# BT_ADOL_R4.net
KiCad netlist of a schematic drawn in EAGLE
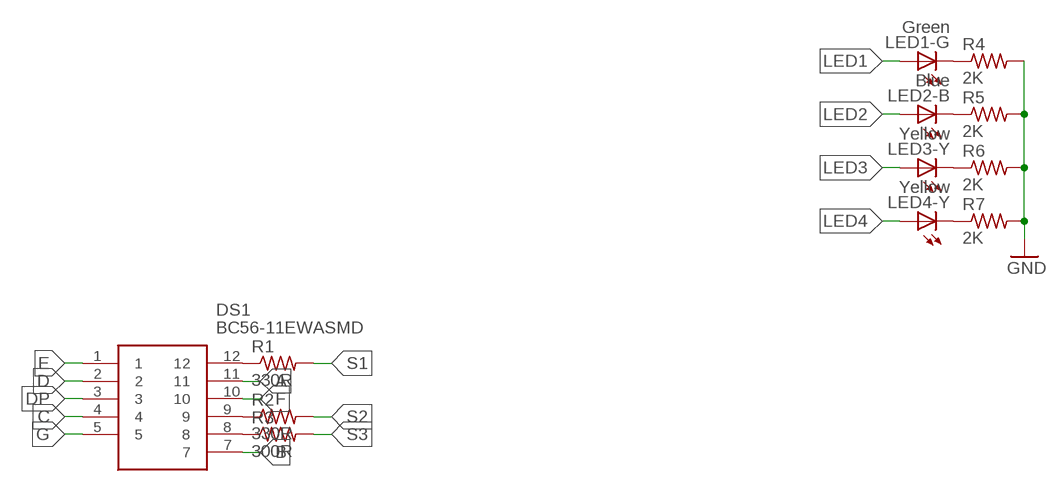
[diagram p0: schematic, sheet 1, part 1 of 2]
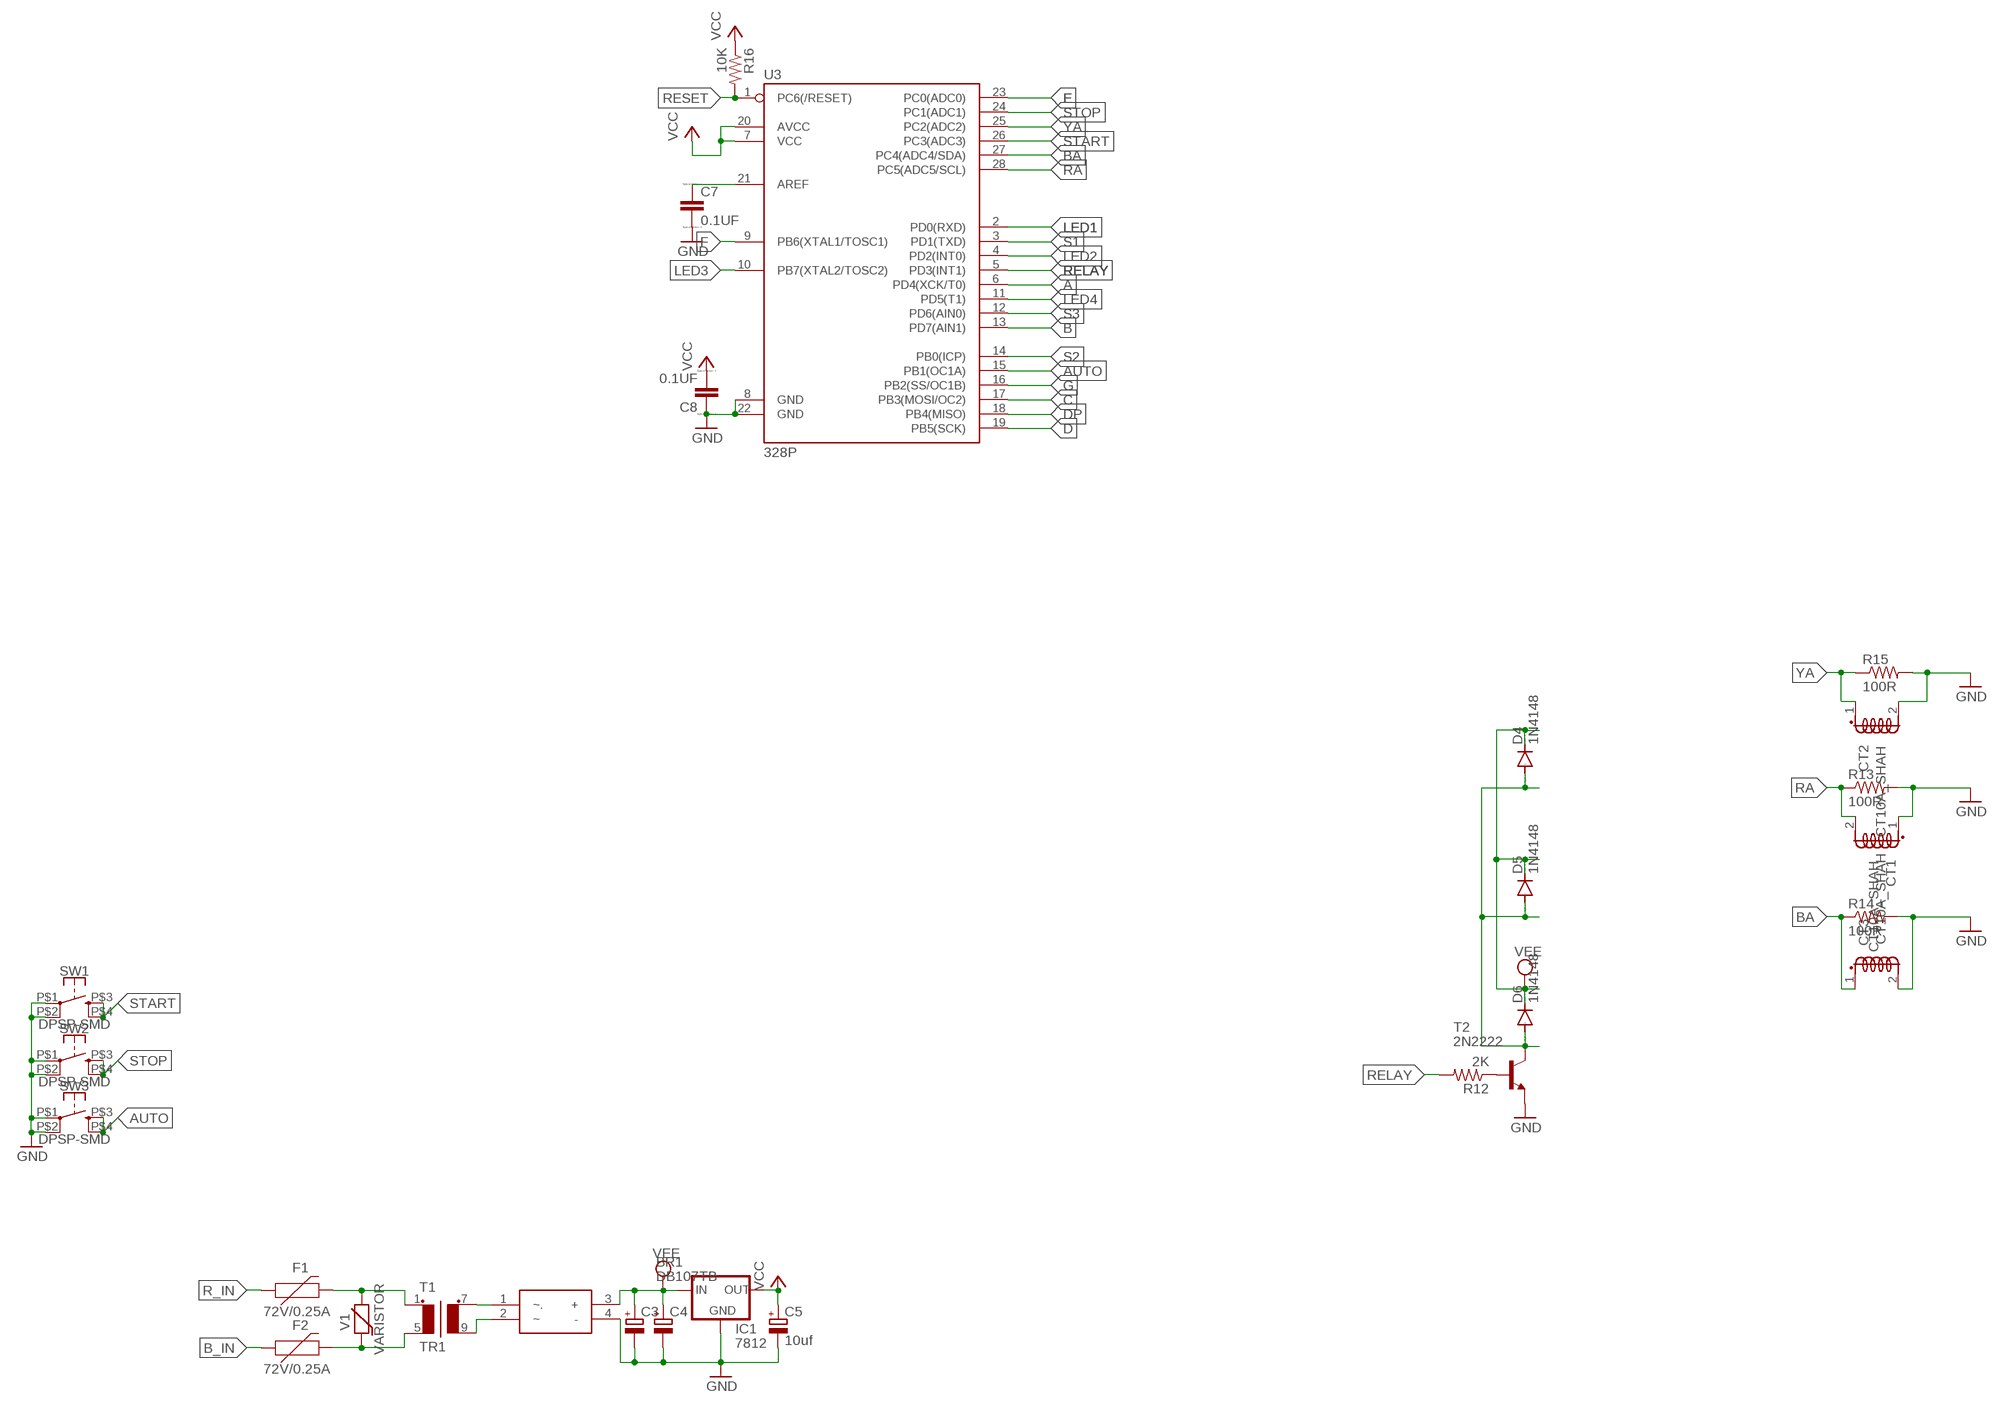
[diagram p1: schematic, sheet 1, part 2 of 2]

(export (version "E")
  (design (tool "Eeschema 10.0.6"))
  (components
    (comp (ref "BR1")
      (value "DB107TB")
      (footprint "eagle-import:DIP845W60P510L815H400Q4N")
      (libsource (lib "eagle-import") (part "DB107TB"))
    )
    (comp (ref "C3")
      (value "CPOL-EUE3.5-10")
      (footprint "eagle-import:E3,5-10")
      (libsource (lib "eagle-import") (part "resistor_348_CPOL-EUE3.5-10"))
    )
    (comp (ref "C4")
      (value "CPOL-EUE3.5-10")
      (footprint "eagle-import:E3,5-10")
      (libsource (lib "eagle-import") (part "resistor_348_CPOL-EUE3.5-10"))
    )
    (comp (ref "C5")
      (value "10uf")
      (footprint "eagle-import:E2-4")
      (libsource (lib "eagle-import") (part "CPOL-EUE2-4"))
    )
    (comp (ref "C7")
      (value "0.1UF")
      (footprint "eagle-import:C1206")
      (libsource (lib "eagle-import") (part "CC1206"))
    )
    (comp (ref "C8")
      (value "0.1UF")
      (footprint "eagle-import:C1206")
      (libsource (lib "eagle-import") (part "CC1206"))
    )
    (comp (ref "CT1")
      (value "CT10A_SHAH")
      (footprint "eagle-import:10A_SHAH")
      (libsource (lib "eagle-import") (part "CT10A_SHAH"))
    )
    (comp (ref "CT2")
      (value "CT10A_SHAH")
      (footprint "eagle-import:10A_SHAH")
      (libsource (lib "eagle-import") (part "CT10A_SHAH"))
    )
    (comp (ref "CT3")
      (value "CT10A_SHAH")
      (footprint "eagle-import:10A_SHAH")
      (libsource (lib "eagle-import") (part "CT10A_SHAH"))
    )
    (comp (ref "D4")
      (value "1N4148")
      (footprint "eagle-import:MINIMELF")
      (libsource (lib "eagle-import") (part "DIODE-MINIMELF"))
    )
    (comp (ref "D5")
      (value "1N4148")
      (footprint "eagle-import:MINIMELF")
      (libsource (lib "eagle-import") (part "DIODE-MINIMELF"))
    )
    (comp (ref "D6")
      (value "1N4148")
      (footprint "eagle-import:MINIMELF")
      (libsource (lib "eagle-import") (part "DIODE-MINIMELF"))
    )
    (comp (ref "DS1")
      (value "BC56-11EWASMD")
      (footprint "eagle-import:7SEGMENT-SMD")
      (libsource (lib "eagle-import") (part "BC56-11EWASMD"))
    )
    (comp (ref "F1")
      (value "72V/0.25A")
      (footprint "eagle-import:PTH")
      (libsource (lib "eagle-import") (part "PPTC_PTH"))
    )
    (comp (ref "F2")
      (value "72V/0.25A")
      (footprint "eagle-import:PTH")
      (libsource (lib "eagle-import") (part "PPTC_PTH"))
    )
    (comp (ref "IC1")
      (value "7812")
      (footprint "eagle-import:78XXS")
      (libsource (lib "eagle-import") (part "78XXS"))
    )
    (comp (ref "LED1-G")
      (value "Green")
      (footprint "eagle-import:LED3MM")
      (libsource (lib "eagle-import") (part "LED3MM"))
    )
    (comp (ref "LED2-B")
      (value "Blue")
      (footprint "eagle-import:LED3MM")
      (libsource (lib "eagle-import") (part "LED3MM"))
    )
    (comp (ref "LED3-Y")
      (value "Yellow")
      (footprint "eagle-import:LED3MM")
      (libsource (lib "eagle-import") (part "LED3MM"))
    )
    (comp (ref "LED4-Y")
      (value "Yellow")
      (footprint "eagle-import:LED3MM")
      (libsource (lib "eagle-import") (part "LED3MM"))
    )
    (comp (ref "R1")
      (value "330R")
      (footprint "eagle-import:R1206")
      (libsource (lib "eagle-import") (part "rcl_334_R-US_R1206"))
    )
    (comp (ref "R2")
      (value "330R")
      (footprint "eagle-import:R1206")
      (libsource (lib "eagle-import") (part "rcl_334_R-US_R1206"))
    )
    (comp (ref "R3")
      (value "300R")
      (footprint "eagle-import:R1206")
      (libsource (lib "eagle-import") (part "rcl_334_R-US_R1206"))
    )
    (comp (ref "R4")
      (value "2K")
      (footprint "eagle-import:R1206")
      (libsource (lib "eagle-import") (part "rcl_334_R-US_R1206"))
    )
    (comp (ref "R5")
      (value "2K")
      (footprint "eagle-import:R1206")
      (libsource (lib "eagle-import") (part "rcl_334_R-US_R1206"))
    )
    (comp (ref "R6")
      (value "2K")
      (footprint "eagle-import:R1206")
      (libsource (lib "eagle-import") (part "rcl_334_R-US_R1206"))
    )
    (comp (ref "R7")
      (value "2K")
      (footprint "eagle-import:R1206")
      (libsource (lib "eagle-import") (part "rcl_334_R-US_R1206"))
    )
    (comp (ref "R12")
      (value "2K")
      (footprint "eagle-import:M1206")
      (libsource (lib "eagle-import") (part "R-US_M1206"))
    )
    (comp (ref "R13")
      (value "100R")
      (footprint "eagle-import:M1206")
      (libsource (lib "eagle-import") (part "R-US_M1206"))
    )
    (comp (ref "R14")
      (value "100R")
      (footprint "eagle-import:M1206")
      (libsource (lib "eagle-import") (part "R-US_M1206"))
    )
    (comp (ref "R15")
      (value "100R")
      (footprint "eagle-import:M1206")
      (libsource (lib "eagle-import") (part "R-US_M1206"))
    )
    (comp (ref "R16")
      (value "10K")
      (footprint "eagle-import:M1206")
      (libsource (lib "eagle-import") (part "R-US_M1206"))
    )
    (comp (ref "SW1")
      (value "DPSP-SMD")
      (footprint "eagle-import:B3F-40XX-ROUND-SMD")
      (libsource (lib "eagle-import") (part "DPSP-SMD"))
    )
    (comp (ref "SW2")
      (value "DPSP-SMD")
      (footprint "eagle-import:B3F-40XX-ROUND-SMD")
      (libsource (lib "eagle-import") (part "DPSP-SMD"))
    )
    (comp (ref "SW3")
      (value "DPSP-SMD")
      (footprint "eagle-import:B3F-40XX-ROUND-SMD")
      (libsource (lib "eagle-import") (part "DPSP-SMD"))
    )
    (comp (ref "T1")
      (value "TR1")
      (footprint "eagle-import:44022012")
      (libsource (lib "eagle-import") (part "TR1"))
    )
    (comp (ref "T2")
      (value "2N2222")
      (footprint "eagle-import:TO92-EBC-OVAL")
      (libsource (lib "eagle-import") (part "2N2222"))
    )
    (comp (ref "U3")
      (value "328P")
      (footprint "eagle-import:DIP28")
      (libsource (lib "eagle-import") (part "ATMEGA328P_PDIP"))
    )
    (comp (ref "V1")
      (value "VARISTOR")
      (footprint "eagle-import:10MM")
      (libsource (lib "eagle-import") (part "VARISTOR"))
    )
  )
  (nets
    (net (code "1") (name "A") (class "Default")
      (node (ref "DS1") (pin "11") (pinfunction "11_11") (pintype "bidirectional"))
      (node (ref "U3") (pin "6") (pinfunction "PD4(XCK/T0)_6") (pintype "bidirectional"))
    )
    (net (code "2") (name "AUTO") (class "Default")
      (node (ref "SW3") (pin "P$3") (pinfunction "3_P$3") (pintype "passive"))
      (node (ref "SW3") (pin "P$4") (pinfunction "4_P$4") (pintype "passive"))
      (node (ref "U3") (pin "15") (pinfunction "PB1(OC1A)_15") (pintype "bidirectional"))
    )
    (net (code "3") (name "B") (class "Default")
      (node (ref "DS1") (pin "7") (pinfunction "7_7") (pintype "bidirectional"))
      (node (ref "U3") (pin "13") (pinfunction "PD7(AIN1)_13") (pintype "bidirectional"))
    )
    (net (code "4") (name "BA") (class "Default")
      (node (ref "CT3") (pin "1") (pinfunction "S1.1_1") (pintype "passive"))
      (node (ref "R14") (pin "1") (pinfunction "1_1") (pintype "passive"))
      (node (ref "U3") (pin "27") (pinfunction "PC4(ADC4/SDA)_27") (pintype "bidirectional"))
    )
    (net (code "5") (name "B_IN") (class "Default")
      (node (ref "F2") (pin "P$1") (pinfunction "1_P$1") (pintype "bidirectional"))
    )
    (net (code "6") (name "C") (class "Default")
      (node (ref "DS1") (pin "4") (pinfunction "4_4") (pintype "bidirectional"))
      (node (ref "U3") (pin "17") (pinfunction "PB3(MOSI/OC2)_17") (pintype "bidirectional"))
    )
    (net (code "7") (name "D") (class "Default")
      (node (ref "DS1") (pin "2") (pinfunction "2_2") (pintype "bidirectional"))
      (node (ref "U3") (pin "19") (pinfunction "PB5(SCK)_19") (pintype "bidirectional"))
    )
    (net (code "8") (name "DP") (class "Default")
      (node (ref "DS1") (pin "3") (pinfunction "3_3") (pintype "bidirectional"))
      (node (ref "U3") (pin "18") (pinfunction "PB4(MISO)_18") (pintype "bidirectional"))
    )
    (net (code "9") (name "E") (class "Default")
      (node (ref "DS1") (pin "1") (pinfunction "1_1") (pintype "bidirectional"))
      (node (ref "U3") (pin "23") (pinfunction "PC0(ADC0)_23") (pintype "bidirectional"))
    )
    (net (code "10") (name "F") (class "Default")
      (node (ref "DS1") (pin "10") (pinfunction "10_10") (pintype "bidirectional"))
      (node (ref "U3") (pin "9") (pinfunction "PB6(XTAL1/TOSC1)_9") (pintype "bidirectional"))
    )
    (net (code "11") (name "G") (class "Default")
      (node (ref "DS1") (pin "5") (pinfunction "5_5") (pintype "bidirectional"))
      (node (ref "U3") (pin "16") (pinfunction "PB2(SS/OC1B)_16") (pintype "bidirectional"))
    )
    (net (code "12") (name "GND") (class "Default")
      (node (ref "BR1") (pin "4") (pinfunction "-_4") (pintype "bidirectional"))
      (node (ref "C3") (pin "-") (pinfunction "-_-") (pintype "passive"))
      (node (ref "C4") (pin "-") (pinfunction "-_-") (pintype "passive"))
      (node (ref "C5") (pin "-") (pinfunction "-_-") (pintype "passive"))
      (node (ref "C7") (pin "2") (pinfunction "2_2") (pintype "passive"))
      (node (ref "C8") (pin "1") (pinfunction "1_1") (pintype "passive"))
      (node (ref "CT1") (pin "1") (pinfunction "S1.1_1") (pintype "passive"))
      (node (ref "CT2") (pin "2") (pinfunction "S1.2_2") (pintype "passive"))
      (node (ref "CT3") (pin "2") (pinfunction "S1.2_2") (pintype "passive"))
      (node (ref "IC1") (pin "GND") (pinfunction "GND_GND") (pintype "input"))
      (node (ref "R13") (pin "2") (pinfunction "2_2") (pintype "passive"))
      (node (ref "R14") (pin "2") (pinfunction "2_2") (pintype "passive"))
      (node (ref "R15") (pin "2") (pinfunction "2_2") (pintype "passive"))
      (node (ref "R4") (pin "2") (pinfunction "2_2") (pintype "passive"))
      (node (ref "R5") (pin "2") (pinfunction "2_2") (pintype "passive"))
      (node (ref "R6") (pin "2") (pinfunction "2_2") (pintype "passive"))
      (node (ref "R7") (pin "2") (pinfunction "2_2") (pintype "passive"))
      (node (ref "SW1") (pin "P$1") (pinfunction "1_P$1") (pintype "passive"))
      (node (ref "SW1") (pin "P$2") (pinfunction "2_P$2") (pintype "passive"))
      (node (ref "SW2") (pin "P$1") (pinfunction "1_P$1") (pintype "passive"))
      (node (ref "SW2") (pin "P$2") (pinfunction "2_P$2") (pintype "passive"))
      (node (ref "SW3") (pin "P$1") (pinfunction "1_P$1") (pintype "passive"))
      (node (ref "SW3") (pin "P$2") (pinfunction "2_P$2") (pintype "passive"))
      (node (ref "T2") (pin "E") (pinfunction "E_E") (pintype "passive"))
      (node (ref "U3") (pin "22") (pinfunction "GND_22") (pintype "bidirectional"))
      (node (ref "U3") (pin "8") (pinfunction "GND_8") (pintype "bidirectional"))
    )
    (net (code "13") (name "LED1") (class "Default")
      (node (ref "LED1-G") (pin "A") (pinfunction "A_A") (pintype "passive"))
      (node (ref "U3") (pin "2") (pinfunction "PD0(RXD)_2") (pintype "bidirectional"))
    )
    (net (code "14") (name "LED2") (class "Default")
      (node (ref "LED2-B") (pin "A") (pinfunction "A_A") (pintype "passive"))
      (node (ref "U3") (pin "4") (pinfunction "PD2(INT0)_4") (pintype "bidirectional"))
    )
    (net (code "15") (name "LED3") (class "Default")
      (node (ref "LED3-Y") (pin "A") (pinfunction "A_A") (pintype "passive"))
      (node (ref "U3") (pin "10") (pinfunction "PB7(XTAL2/TOSC2)_10") (pintype "bidirectional"))
    )
    (net (code "16") (name "LED4") (class "Default")
      (node (ref "LED4-Y") (pin "A") (pinfunction "A_A") (pintype "passive"))
      (node (ref "U3") (pin "11") (pinfunction "PD5(T1)_11") (pintype "bidirectional"))
    )
    (net (code "17") (name "Net-(BR1-~)") (class "Default")
      (node (ref "BR1") (pin "2") (pinfunction "~_2") (pintype "bidirectional"))
      (node (ref "T1") (pin "9") (pinfunction "S2_9") (pintype "passive"))
    )
    (net (code "18") (name "Net-(BR1-~{.})") (class "Default")
      (node (ref "BR1") (pin "1") (pinfunction "~{.}_1") (pintype "bidirectional"))
      (node (ref "T1") (pin "7") (pinfunction "S1_7") (pintype "passive"))
    )
    (net (code "19") (name "Net-(D4-PadA)") (class "Default")
      (node (ref "D4") (pin "A") (pinfunction "A_A") (pintype "passive"))
      (node (ref "D5") (pin "A") (pinfunction "A_A") (pintype "passive"))
      (node (ref "D6") (pin "A") (pinfunction "A_A") (pintype "passive"))
      (node (ref "T2") (pin "C") (pinfunction "C_C") (pintype "passive"))
    )
    (net (code "20") (name "Net-(DS1-Pad8)") (class "Default")
      (node (ref "DS1") (pin "8") (pinfunction "8_8") (pintype "bidirectional"))
      (node (ref "R3") (pin "1") (pinfunction "1_1") (pintype "passive"))
    )
    (net (code "21") (name "Net-(DS1-Pad9)") (class "Default")
      (node (ref "DS1") (pin "9") (pinfunction "9_9") (pintype "bidirectional"))
      (node (ref "R2") (pin "1") (pinfunction "1_1") (pintype "passive"))
    )
    (net (code "22") (name "Net-(DS1-Pad12)") (class "Default")
      (node (ref "DS1") (pin "12") (pinfunction "12_12") (pintype "bidirectional"))
      (node (ref "R1") (pin "1") (pinfunction "1_1") (pintype "passive"))
    )
    (net (code "23") (name "Net-(F1-2)") (class "Default")
      (node (ref "F1") (pin "P$2") (pinfunction "2_P$2") (pintype "bidirectional"))
      (node (ref "T1") (pin "1") (pinfunction "P1_1") (pintype "passive"))
      (node (ref "V1") (pin "2") (pinfunction "2_2") (pintype "passive"))
    )
    (net (code "24") (name "Net-(F2-2)") (class "Default")
      (node (ref "F2") (pin "P$2") (pinfunction "2_P$2") (pintype "bidirectional"))
      (node (ref "T1") (pin "5") (pinfunction "P2_5") (pintype "passive"))
      (node (ref "V1") (pin "1") (pinfunction "1_1") (pintype "passive"))
    )
    (net (code "25") (name "Net-(LED1-G-C)") (class "Default")
      (node (ref "LED1-G") (pin "K") (pinfunction "C_K") (pintype "passive"))
      (node (ref "R4") (pin "1") (pinfunction "1_1") (pintype "passive"))
    )
    (net (code "26") (name "Net-(LED2-B-C)") (class "Default")
      (node (ref "LED2-B") (pin "K") (pinfunction "C_K") (pintype "passive"))
      (node (ref "R5") (pin "1") (pinfunction "1_1") (pintype "passive"))
    )
    (net (code "27") (name "Net-(LED3-Y-C)") (class "Default")
      (node (ref "LED3-Y") (pin "K") (pinfunction "C_K") (pintype "passive"))
      (node (ref "R6") (pin "1") (pinfunction "1_1") (pintype "passive"))
    )
    (net (code "28") (name "Net-(LED4-Y-C)") (class "Default")
      (node (ref "LED4-Y") (pin "K") (pinfunction "C_K") (pintype "passive"))
      (node (ref "R7") (pin "1") (pinfunction "1_1") (pintype "passive"))
    )
    (net (code "29") (name "Net-(R12-Pad1)") (class "Default")
      (node (ref "R12") (pin "1") (pinfunction "1_1") (pintype "passive"))
      (node (ref "T2") (pin "B") (pinfunction "B_B") (pintype "passive"))
    )
    (net (code "30") (name "Net-(U3-AREF)") (class "Default")
      (node (ref "C7") (pin "1") (pinfunction "1_1") (pintype "passive"))
      (node (ref "U3") (pin "21") (pinfunction "AREF_21") (pintype "bidirectional"))
    )
    (net (code "31") (name "RA") (class "Default")
      (node (ref "CT1") (pin "2") (pinfunction "S1.2_2") (pintype "passive"))
      (node (ref "R13") (pin "1") (pinfunction "1_1") (pintype "passive"))
      (node (ref "U3") (pin "28") (pinfunction "PC5(ADC5/SCL)_28") (pintype "bidirectional"))
    )
    (net (code "32") (name "RELAY") (class "Default")
      (node (ref "R12") (pin "2") (pinfunction "2_2") (pintype "passive"))
      (node (ref "U3") (pin "5") (pinfunction "PD3(INT1)_5") (pintype "bidirectional"))
    )
    (net (code "33") (name "RESET") (class "Default")
      (node (ref "R16") (pin "2") (pinfunction "2_2") (pintype "passive"))
      (node (ref "U3") (pin "1") (pinfunction "PC6(/RESET)_1") (pintype "bidirectional"))
    )
    (net (code "34") (name "R_IN") (class "Default")
      (node (ref "F1") (pin "P$1") (pinfunction "1_P$1") (pintype "bidirectional"))
    )
    (net (code "35") (name "S1") (class "Default")
      (node (ref "R1") (pin "2") (pinfunction "2_2") (pintype "passive"))
      (node (ref "U3") (pin "3") (pinfunction "PD1(TXD)_3") (pintype "bidirectional"))
    )
    (net (code "36") (name "S2") (class "Default")
      (node (ref "R2") (pin "2") (pinfunction "2_2") (pintype "passive"))
      (node (ref "U3") (pin "14") (pinfunction "PB0(ICP)_14") (pintype "bidirectional"))
    )
    (net (code "37") (name "S3") (class "Default")
      (node (ref "R3") (pin "2") (pinfunction "2_2") (pintype "passive"))
      (node (ref "U3") (pin "12") (pinfunction "PD6(AIN0)_12") (pintype "bidirectional"))
    )
    (net (code "38") (name "START") (class "Default")
      (node (ref "SW1") (pin "P$3") (pinfunction "3_P$3") (pintype "passive"))
      (node (ref "SW1") (pin "P$4") (pinfunction "4_P$4") (pintype "passive"))
      (node (ref "U3") (pin "26") (pinfunction "PC3(ADC3)_26") (pintype "bidirectional"))
    )
    (net (code "39") (name "STOP") (class "Default")
      (node (ref "SW2") (pin "P$3") (pinfunction "3_P$3") (pintype "passive"))
      (node (ref "SW2") (pin "P$4") (pinfunction "4_P$4") (pintype "passive"))
      (node (ref "U3") (pin "24") (pinfunction "PC1(ADC1)_24") (pintype "bidirectional"))
    )
    (net (code "40") (name "VCC") (class "Default")
      (node (ref "C5") (pin "+") (pinfunction "+_+") (pintype "passive"))
      (node (ref "C8") (pin "2") (pinfunction "2_2") (pintype "passive"))
      (node (ref "IC1") (pin "OUT") (pinfunction "OUT_OUT") (pintype "passive"))
      (node (ref "R16") (pin "1") (pinfunction "1_1") (pintype "passive"))
      (node (ref "U3") (pin "20") (pinfunction "AVCC_20") (pintype "bidirectional"))
      (node (ref "U3") (pin "7") (pinfunction "VCC_7") (pintype "bidirectional"))
    )
    (net (code "41") (name "VEE") (class "Default")
      (node (ref "BR1") (pin "3") (pinfunction "+_3") (pintype "bidirectional"))
      (node (ref "C3") (pin "+") (pinfunction "+_+") (pintype "passive"))
      (node (ref "C4") (pin "+") (pinfunction "+_+") (pintype "passive"))
      (node (ref "D4") (pin "C") (pinfunction "C_C") (pintype "passive"))
      (node (ref "D5") (pin "C") (pinfunction "C_C") (pintype "passive"))
      (node (ref "D6") (pin "C") (pinfunction "C_C") (pintype "passive"))
      (node (ref "IC1") (pin "IN") (pinfunction "IN_IN") (pintype "input"))
    )
    (net (code "42") (name "YA") (class "Default")
      (node (ref "CT2") (pin "1") (pinfunction "S1.1_1") (pintype "passive"))
      (node (ref "R15") (pin "1") (pinfunction "1_1") (pintype "passive"))
      (node (ref "U3") (pin "25") (pinfunction "PC2(ADC2)_25") (pintype "bidirectional"))
    )
  )
)
